# partybooth.net
KiCad netlist of a schematic drawn in EAGLE
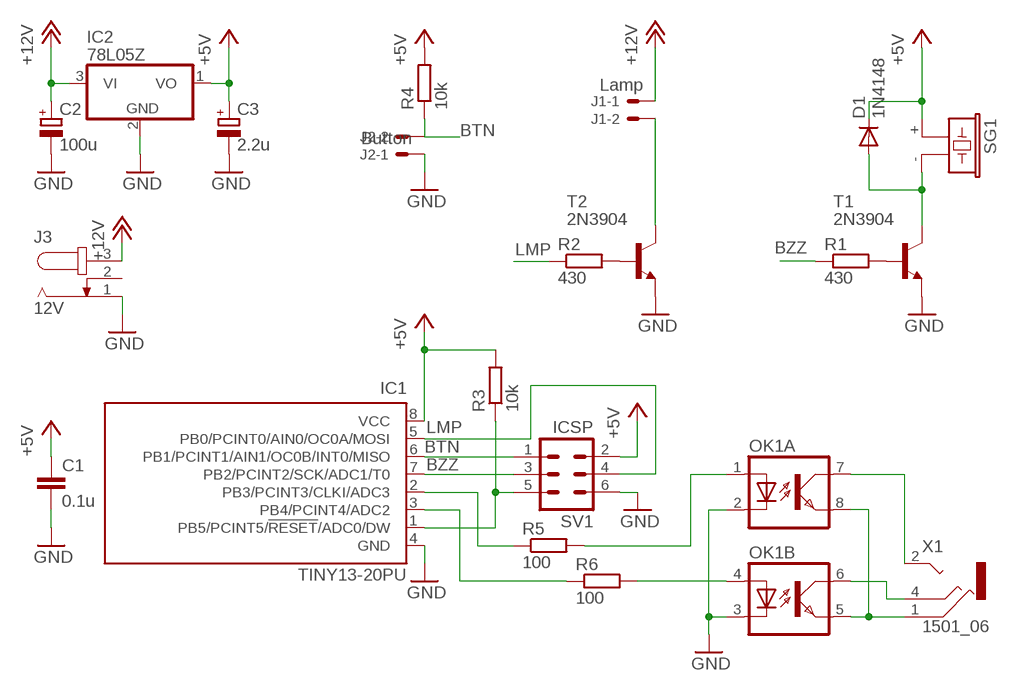
[diagram p0: schematic, sheet 1]

(export (version "E")
  (design (tool "Eeschema 10.0.6"))
  (components
    (comp (ref "C1")
      (value "0.1u")
      (footprint "eagle-import:C025_050-025X075")
      (libsource (lib "eagle-import") (part "C-EU025_050-025X075"))
    )
    (comp (ref "C2")
      (value "100u")
      (footprint "eagle-import:B45181B")
      (libsource (lib "eagle-import") (part "CPOL-EUB45181B"))
    )
    (comp (ref "C3")
      (value "2.2u")
      (footprint "eagle-import:B45181B")
      (libsource (lib "eagle-import") (part "CPOL-EUB45181B"))
    )
    (comp (ref "D1")
      (value "1N4148")
      (footprint "eagle-import:DO35-7")
      (libsource (lib "eagle-import") (part "1N4148DO35-7"))
    )
    (comp (ref "IC1")
      (value "TINY13-20PU")
      (footprint "eagle-import:DIL08")
      (fields (field (name "MPN") "ATTINY13-20PU"))
      (libsource (lib "eagle-import") (part "TINY13PU-20"))
    )
    (comp (ref "IC2")
      (value "78L05Z")
      (footprint "eagle-import:TO92")
      (libsource (lib "eagle-import") (part "78ZL05"))
    )
    (comp (ref "J1")
      (value "Lamp")
      (footprint "eagle-import:6410-02")
      (libsource (lib "eagle-import") (part "22-?-0227-2021"))
    )
    (comp (ref "J2")
      (value "Button")
      (footprint "eagle-import:6410-02")
      (libsource (lib "eagle-import") (part "22-?-0227-2021"))
    )
    (comp (ref "J3")
      (value "12V")
      (footprint "eagle-import:SPC4077")
      (libsource (lib "eagle-import") (part "JACK-PLUG0"))
    )
    (comp (ref "OK1")
      (value "ILD2")
      (footprint "eagle-import:DIL08")
      (libsource (lib "eagle-import") (part "ILD2"))
    )
    (comp (ref "R1")
      (value "430")
      (footprint "eagle-import:0204_7")
      (libsource (lib "eagle-import") (part "R-EU_0204/7"))
    )
    (comp (ref "R2")
      (value "430")
      (footprint "eagle-import:0204_7")
      (libsource (lib "eagle-import") (part "R-EU_0204/7"))
    )
    (comp (ref "R3")
      (value "10k")
      (footprint "eagle-import:0204_7")
      (libsource (lib "eagle-import") (part "R-EU_0204/7"))
    )
    (comp (ref "R4")
      (value "10k")
      (footprint "eagle-import:0204_7")
      (libsource (lib "eagle-import") (part "R-EU_0204/7"))
    )
    (comp (ref "R5")
      (value "100")
      (footprint "eagle-import:0204_7")
      (libsource (lib "eagle-import") (part "R-EU_0204/7"))
    )
    (comp (ref "R6")
      (value "100")
      (footprint "eagle-import:0204_7")
      (libsource (lib "eagle-import") (part "R-EU_0204/7"))
    )
    (comp (ref "SG1")
      (value "F/CM12P")
      (footprint "eagle-import:F_CM12P")
      (libsource (lib "eagle-import") (part "F/CM12P"))
    )
    (comp (ref "SV1")
      (value "ICSP")
      (footprint "eagle-import:MA03-2")
      (libsource (lib "eagle-import") (part "MA03-2"))
    )
    (comp (ref "T1")
      (value "2N3904")
      (footprint "eagle-import:TO92")
      (libsource (lib "eagle-import") (part "2N3904"))
    )
    (comp (ref "T2")
      (value "2N3904")
      (footprint "eagle-import:TO92")
      (libsource (lib "eagle-import") (part "2N3904"))
    )
    (comp (ref "X1")
      (value "1501_06")
      (footprint "eagle-import:1501_06")
      (libsource (lib "eagle-import") (part "1501_06"))
    )
  )
  (nets
    (net (code "1") (name "+5V") (class "Default")
      (node (ref "C1") (pin "1") (pinfunction "1_1") (pintype "passive"))
      (node (ref "C3") (pin "+") (pinfunction "+_+") (pintype "passive"))
      (node (ref "D1") (pin "C") (pinfunction "C_C") (pintype "passive"))
      (node (ref "IC1") (pin "8") (pinfunction "VCC_8") (pintype "power_in"))
      (node (ref "IC2") (pin "1") (pinfunction "VO_1") (pintype "passive"))
      (node (ref "R3") (pin "2") (pinfunction "2_2") (pintype "passive"))
      (node (ref "R4") (pin "2") (pinfunction "2_2") (pintype "passive"))
      (node (ref "SG1") (pin "+") (pinfunction "1_+") (pintype "passive"))
      (node (ref "SV1") (pin "2") (pinfunction "2_2") (pintype "passive"))
    )
    (net (code "2") (name "+12V") (class "Default")
      (node (ref "C2") (pin "+") (pinfunction "+_+") (pintype "passive"))
      (node (ref "IC2") (pin "3") (pinfunction "VI_3") (pintype "input"))
      (node (ref "J1") (pin "1") (pinfunction "S_1") (pintype "passive"))
      (node (ref "J3") (pin "3") (pinfunction "3_3") (pintype "passive"))
    )
    (net (code "3") (name "/BTN") (class "Default")
      (node (ref "IC1") (pin "6") (pinfunction "PB1/PCINT1/AIN1/OC0B/INT0/MISO_6") (pintype "bidirectional"))
      (node (ref "J2") (pin "2") (pinfunction "S_2") (pintype "passive"))
      (node (ref "R4") (pin "1") (pinfunction "1_1") (pintype "passive"))
      (node (ref "SV1") (pin "1") (pinfunction "1_1") (pintype "passive"))
    )
    (net (code "4") (name "/BZZ") (class "Default")
      (node (ref "IC1") (pin "7") (pinfunction "PB2/PCINT2/SCK/ADC1/T0_7") (pintype "bidirectional"))
      (node (ref "R1") (pin "1") (pinfunction "1_1") (pintype "passive"))
      (node (ref "SV1") (pin "3") (pinfunction "3_3") (pintype "passive"))
    )
    (net (code "5") (name "/LMP") (class "Default")
      (node (ref "IC1") (pin "5") (pinfunction "PB0/PCINT0/AIN0/OC0A/MOSI_5") (pintype "bidirectional"))
      (node (ref "R2") (pin "1") (pinfunction "1_1") (pintype "passive"))
      (node (ref "SV1") (pin "4") (pinfunction "4_4") (pintype "passive"))
    )
    (net (code "6") (name "GND") (class "Default")
      (node (ref "C1") (pin "2") (pinfunction "2_2") (pintype "passive"))
      (node (ref "C2") (pin "-") (pinfunction "-_-") (pintype "passive"))
      (node (ref "C3") (pin "-") (pinfunction "-_-") (pintype "passive"))
      (node (ref "IC1") (pin "4") (pinfunction "GND_4") (pintype "power_in"))
      (node (ref "IC2") (pin "2") (pinfunction "GND_2") (pintype "passive"))
      (node (ref "J2") (pin "1") (pinfunction "S_1") (pintype "passive"))
      (node (ref "J3") (pin "1") (pinfunction "1_1") (pintype "passive"))
      (node (ref "OK1") (pin "2") (pinfunction "C_2") (pintype "passive"))
      (node (ref "OK1") (pin "3") (pinfunction "C_3") (pintype "passive"))
      (node (ref "SV1") (pin "6") (pinfunction "6_6") (pintype "passive"))
      (node (ref "T1") (pin "3") (pinfunction "E_3") (pintype "passive"))
      (node (ref "T2") (pin "3") (pinfunction "E_3") (pintype "passive"))
    )
    (net (code "7") (name "Net-(IC1-PB3{slash}PCINT3{slash}CLKI{slash}ADC3)") (class "Default")
      (node (ref "IC1") (pin "2") (pinfunction "PB3/PCINT3/CLKI/ADC3_2") (pintype "bidirectional"))
      (node (ref "R5") (pin "1") (pinfunction "1_1") (pintype "passive"))
    )
    (net (code "8") (name "Net-(IC1-PB4{slash}PCINT4{slash}ADC2)") (class "Default")
      (node (ref "IC1") (pin "3") (pinfunction "PB4/PCINT4/ADC2_3") (pintype "bidirectional"))
      (node (ref "R6") (pin "1") (pinfunction "1_1") (pintype "passive"))
    )
    (net (code "9") (name "Net-(IC1-PB5{slash}PCINT5{slash}~{RESET}{slash}ADC0{slash}DW)") (class "Default")
      (node (ref "IC1") (pin "1") (pinfunction "PB5/PCINT5/~{RESET}/ADC0/DW_1") (pintype "bidirectional"))
      (node (ref "R3") (pin "1") (pinfunction "1_1") (pintype "passive"))
      (node (ref "SV1") (pin "5") (pinfunction "5_5") (pintype "passive"))
    )
    (net (code "10") (name "Net-(J1B-S)") (class "Default")
      (node (ref "J1") (pin "2") (pinfunction "S_2") (pintype "passive"))
      (node (ref "T2") (pin "1") (pinfunction "C_1") (pintype "passive"))
    )
    (net (code "11") (name "Net-(OK1A-A)") (class "Default")
      (node (ref "OK1") (pin "1") (pinfunction "A_1") (pintype "passive"))
      (node (ref "R5") (pin "2") (pinfunction "2_2") (pintype "passive"))
    )
    (net (code "12") (name "Net-(OK1A-COL)") (class "Default")
      (node (ref "OK1") (pin "7") (pinfunction "COL_7") (pintype "passive"))
      (node (ref "X1") (pin "2") (pinfunction "2_2") (pintype "passive"))
    )
    (net (code "13") (name "Net-(OK1A-EMIT)") (class "Default")
      (node (ref "OK1") (pin "5") (pinfunction "EMIT_5") (pintype "passive"))
      (node (ref "OK1") (pin "8") (pinfunction "EMIT_8") (pintype "passive"))
      (node (ref "X1") (pin "1") (pinfunction "1_1") (pintype "passive"))
    )
    (net (code "14") (name "Net-(OK1B-A)") (class "Default")
      (node (ref "OK1") (pin "4") (pinfunction "A_4") (pintype "passive"))
      (node (ref "R6") (pin "2") (pinfunction "2_2") (pintype "passive"))
    )
    (net (code "15") (name "Net-(OK1B-COL)") (class "Default")
      (node (ref "OK1") (pin "6") (pinfunction "COL_6") (pintype "passive"))
      (node (ref "X1") (pin "4") (pinfunction "3_4") (pintype "passive"))
    )
    (net (code "16") (name "Net-(SG1-2)") (class "Default")
      (node (ref "D1") (pin "A") (pinfunction "A_A") (pintype "passive"))
      (node (ref "SG1") (pin "-") (pinfunction "2_-") (pintype "passive"))
      (node (ref "T1") (pin "1") (pinfunction "C_1") (pintype "passive"))
    )
    (net (code "17") (name "Net-(T1-B)") (class "Default")
      (node (ref "R1") (pin "2") (pinfunction "2_2") (pintype "passive"))
      (node (ref "T1") (pin "2") (pinfunction "B_2") (pintype "passive"))
    )
    (net (code "18") (name "Net-(T2-B)") (class "Default")
      (node (ref "R2") (pin "2") (pinfunction "2_2") (pintype "passive"))
      (node (ref "T2") (pin "2") (pinfunction "B_2") (pintype "passive"))
    )
    (net (code "19") (name "unconnected-(J3-Pad2)") (class "Default")
      (node (ref "J3") (pin "2") (pinfunction "2_2") (pintype "passive"))
    )
  )
)
